# RJ11-Breakout.net
KiCad netlist of a schematic drawn in EAGLE
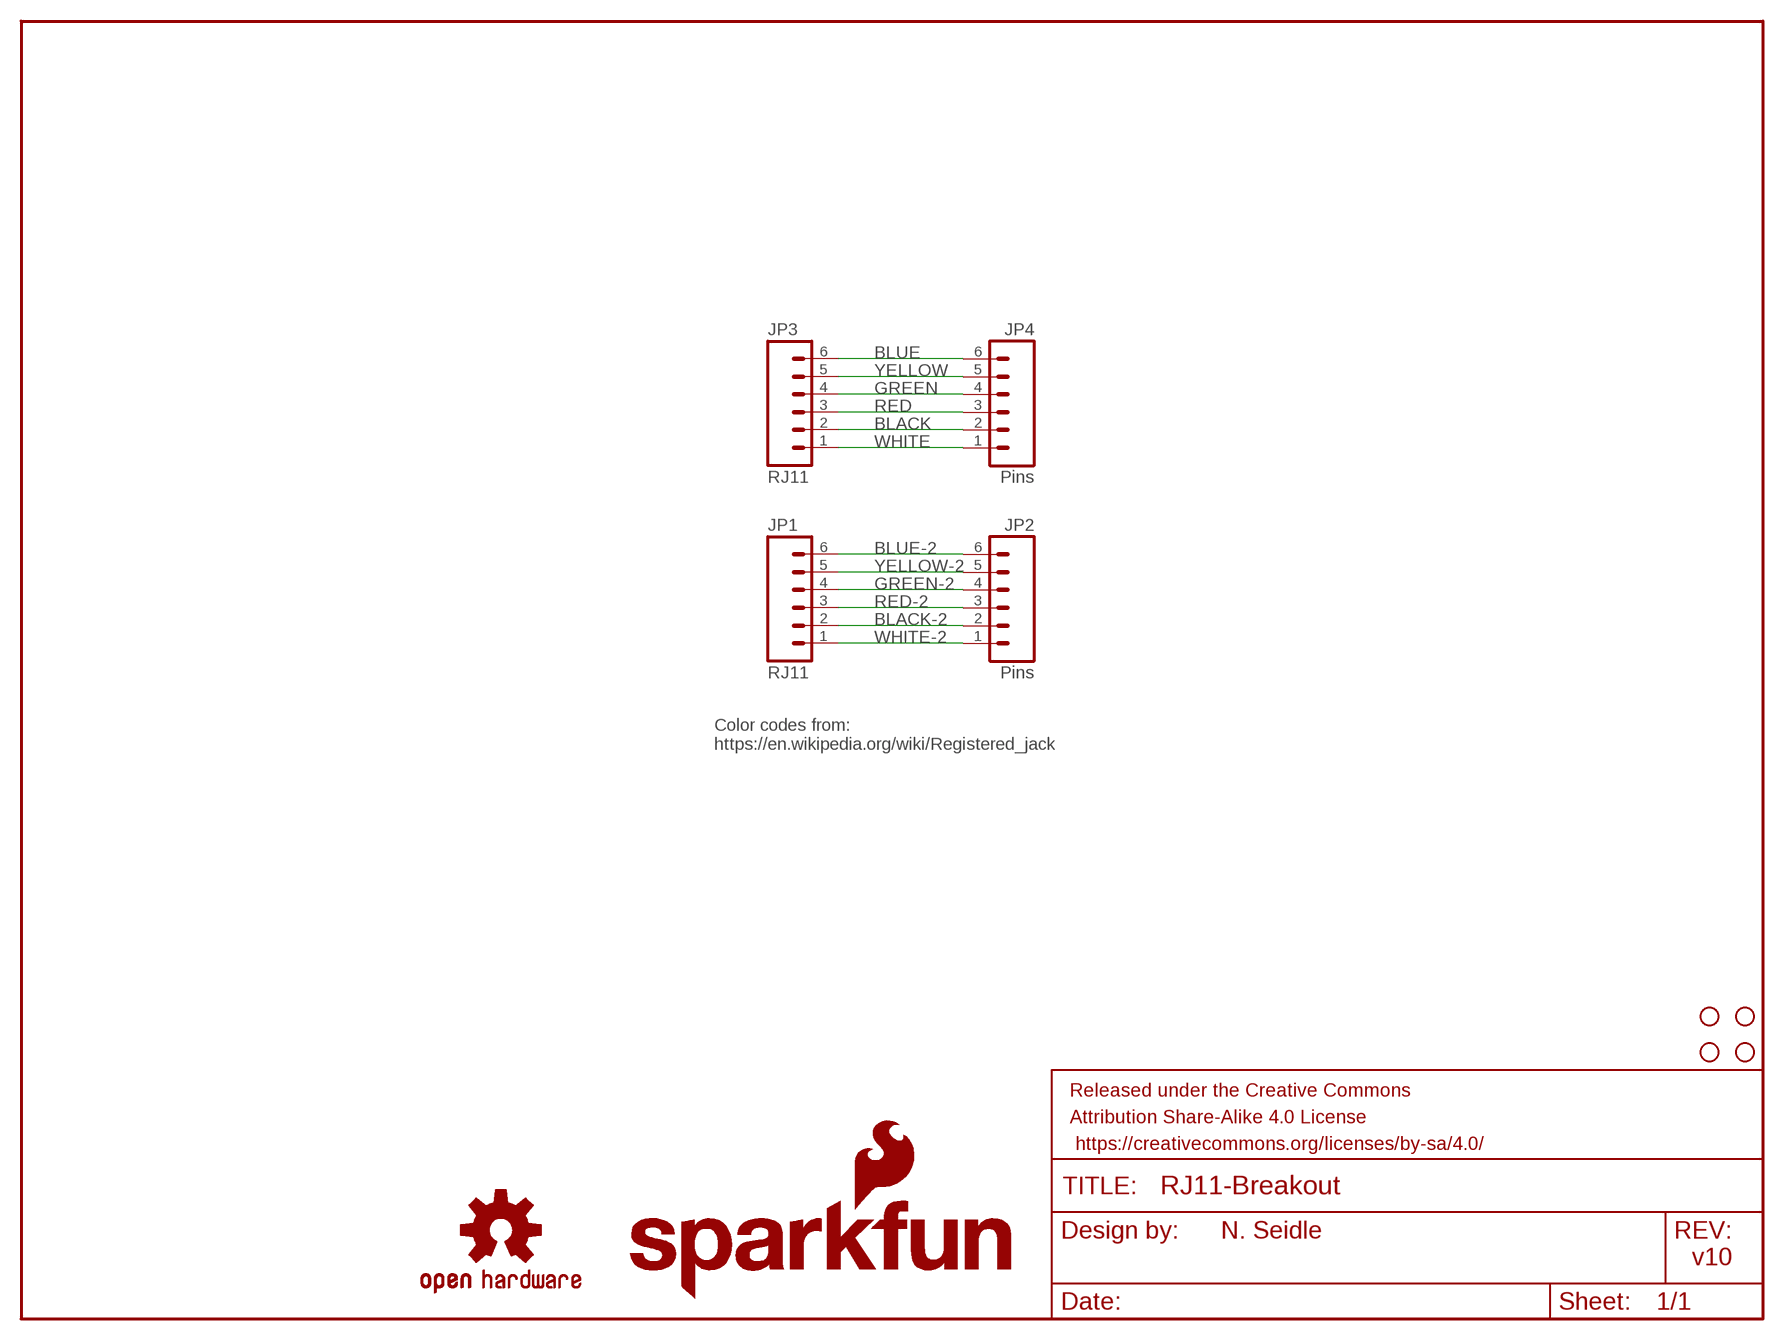
[diagram p0: schematic, sheet 1]

(export (version "E")
  (design (tool "Eeschema 10.0.6"))
  (components
    (comp (ref "FRAME2")
      (value "FRAME-LETTER")
      (footprint "eagle-import:CREATIVE_COMMONS")
      (libsource (lib "eagle-import") (part "FRAME-LETTER"))
    )
    (comp (ref "H1")
      (value "STAND-OFF")
      (footprint "eagle-import:STAND-OFF")
      (libsource (lib "eagle-import") (part "STAND-OFF"))
    )
    (comp (ref "H2")
      (value "STAND-OFF")
      (footprint "eagle-import:STAND-OFF")
      (libsource (lib "eagle-import") (part "STAND-OFF"))
    )
    (comp (ref "H3")
      (value "STAND-OFF")
      (footprint "eagle-import:STAND-OFF")
      (libsource (lib "eagle-import") (part "STAND-OFF"))
    )
    (comp (ref "H4")
      (value "STAND-OFF")
      (footprint "eagle-import:STAND-OFF")
      (libsource (lib "eagle-import") (part "STAND-OFF"))
    )
    (comp (ref "JP1")
      (value "RJ11")
      (footprint "eagle-import:RJ11-6")
      (libsource (lib "eagle-import") (part "RJ11-6PTH"))
    )
    (comp (ref "JP2")
      (value "Pins")
      (footprint "eagle-import:1X06")
      (libsource (lib "eagle-import") (part "M06SILK_FEMALE_PTH"))
    )
    (comp (ref "JP3")
      (value "RJ11")
      (footprint "eagle-import:RJ11-6")
      (libsource (lib "eagle-import") (part "RJ11-6PTH"))
    )
    (comp (ref "JP4")
      (value "Pins")
      (footprint "eagle-import:1X06")
      (libsource (lib "eagle-import") (part "M06SILK_FEMALE_PTH"))
    )
    (comp (ref "LOGO1")
      (value "SFE_LOGO_NAME_FLAME.1_INCH")
      (footprint "eagle-import:SFE_LOGO_NAME_FLAME_.1")
      (libsource (lib "eagle-import") (part "SFE_LOGO_NAME_FLAME.1_INCH"))
    )
    (comp (ref "LOGO2")
      (value "SFE_LOGO_NAME_FLAME.1_INCH")
      (footprint "eagle-import:SFE_LOGO_NAME_FLAME_.1")
      (libsource (lib "eagle-import") (part "SFE_LOGO_NAME_FLAME.1_INCH"))
    )
    (comp (ref "LOGO3")
      (value "OSHW-LOGOMINI")
      (footprint "eagle-import:OSHW-LOGO-MINI")
      (libsource (lib "eagle-import") (part "OSHW-LOGOMINI"))
    )
    (comp (ref "LOGO4")
      (value "SFE_LOGO_NAME_FLAME.1_INCH")
      (footprint "eagle-import:SFE_LOGO_NAME_FLAME_.1")
      (libsource (lib "eagle-import") (part "SFE_LOGO_NAME_FLAME.1_INCH"))
    )
    (comp (ref "LOGO5")
      (value "SFE_LOGO_NAME_FLAME.1_INCH")
      (footprint "eagle-import:SFE_LOGO_NAME_FLAME_.1")
      (libsource (lib "eagle-import") (part "SFE_LOGO_NAME_FLAME.1_INCH"))
    )
    (comp (ref "LOGO6")
      (value "OSHW-LOGOMINI")
      (footprint "eagle-import:OSHW-LOGO-MINI")
      (libsource (lib "eagle-import") (part "OSHW-LOGOMINI"))
    )
  )
  (nets
    (net (code "1") (name "/BLACK") (class "Default")
      (node (ref "JP3") (pin "2") (pinfunction "2_2") (pintype "passive"))
      (node (ref "JP4") (pin "2") (pinfunction "2_2") (pintype "passive"))
    )
    (net (code "2") (name "/BLACK-2") (class "Default")
      (node (ref "JP1") (pin "2") (pinfunction "2_2") (pintype "passive"))
      (node (ref "JP2") (pin "2") (pinfunction "2_2") (pintype "passive"))
    )
    (net (code "3") (name "/BLUE") (class "Default")
      (node (ref "JP3") (pin "6") (pinfunction "6_6") (pintype "passive"))
      (node (ref "JP4") (pin "6") (pinfunction "6_6") (pintype "passive"))
    )
    (net (code "4") (name "/BLUE-2") (class "Default")
      (node (ref "JP1") (pin "6") (pinfunction "6_6") (pintype "passive"))
      (node (ref "JP2") (pin "6") (pinfunction "6_6") (pintype "passive"))
    )
    (net (code "5") (name "/GREEN") (class "Default")
      (node (ref "JP3") (pin "4") (pinfunction "4_4") (pintype "passive"))
      (node (ref "JP4") (pin "4") (pinfunction "4_4") (pintype "passive"))
    )
    (net (code "6") (name "/GREEN-2") (class "Default")
      (node (ref "JP1") (pin "4") (pinfunction "4_4") (pintype "passive"))
      (node (ref "JP2") (pin "4") (pinfunction "4_4") (pintype "passive"))
    )
    (net (code "7") (name "/RED") (class "Default")
      (node (ref "JP3") (pin "3") (pinfunction "3_3") (pintype "passive"))
      (node (ref "JP4") (pin "3") (pinfunction "3_3") (pintype "passive"))
    )
    (net (code "8") (name "/RED-2") (class "Default")
      (node (ref "JP1") (pin "3") (pinfunction "3_3") (pintype "passive"))
      (node (ref "JP2") (pin "3") (pinfunction "3_3") (pintype "passive"))
    )
    (net (code "9") (name "/WHITE") (class "Default")
      (node (ref "JP3") (pin "1") (pinfunction "1_1") (pintype "passive"))
      (node (ref "JP4") (pin "1") (pinfunction "1_1") (pintype "passive"))
    )
    (net (code "10") (name "/WHITE-2") (class "Default")
      (node (ref "JP1") (pin "1") (pinfunction "1_1") (pintype "passive"))
      (node (ref "JP2") (pin "1") (pinfunction "1_1") (pintype "passive"))
    )
    (net (code "11") (name "/YELLOW") (class "Default")
      (node (ref "JP3") (pin "5") (pinfunction "5_5") (pintype "passive"))
      (node (ref "JP4") (pin "5") (pinfunction "5_5") (pintype "passive"))
    )
    (net (code "12") (name "/YELLOW-2") (class "Default")
      (node (ref "JP1") (pin "5") (pinfunction "5_5") (pintype "passive"))
      (node (ref "JP2") (pin "5") (pinfunction "5_5") (pintype "passive"))
    )
  )
)
